# SCH_usb-hub_2024-08-11.net
KiCad netlist of a schematic drawn in EasyEDA
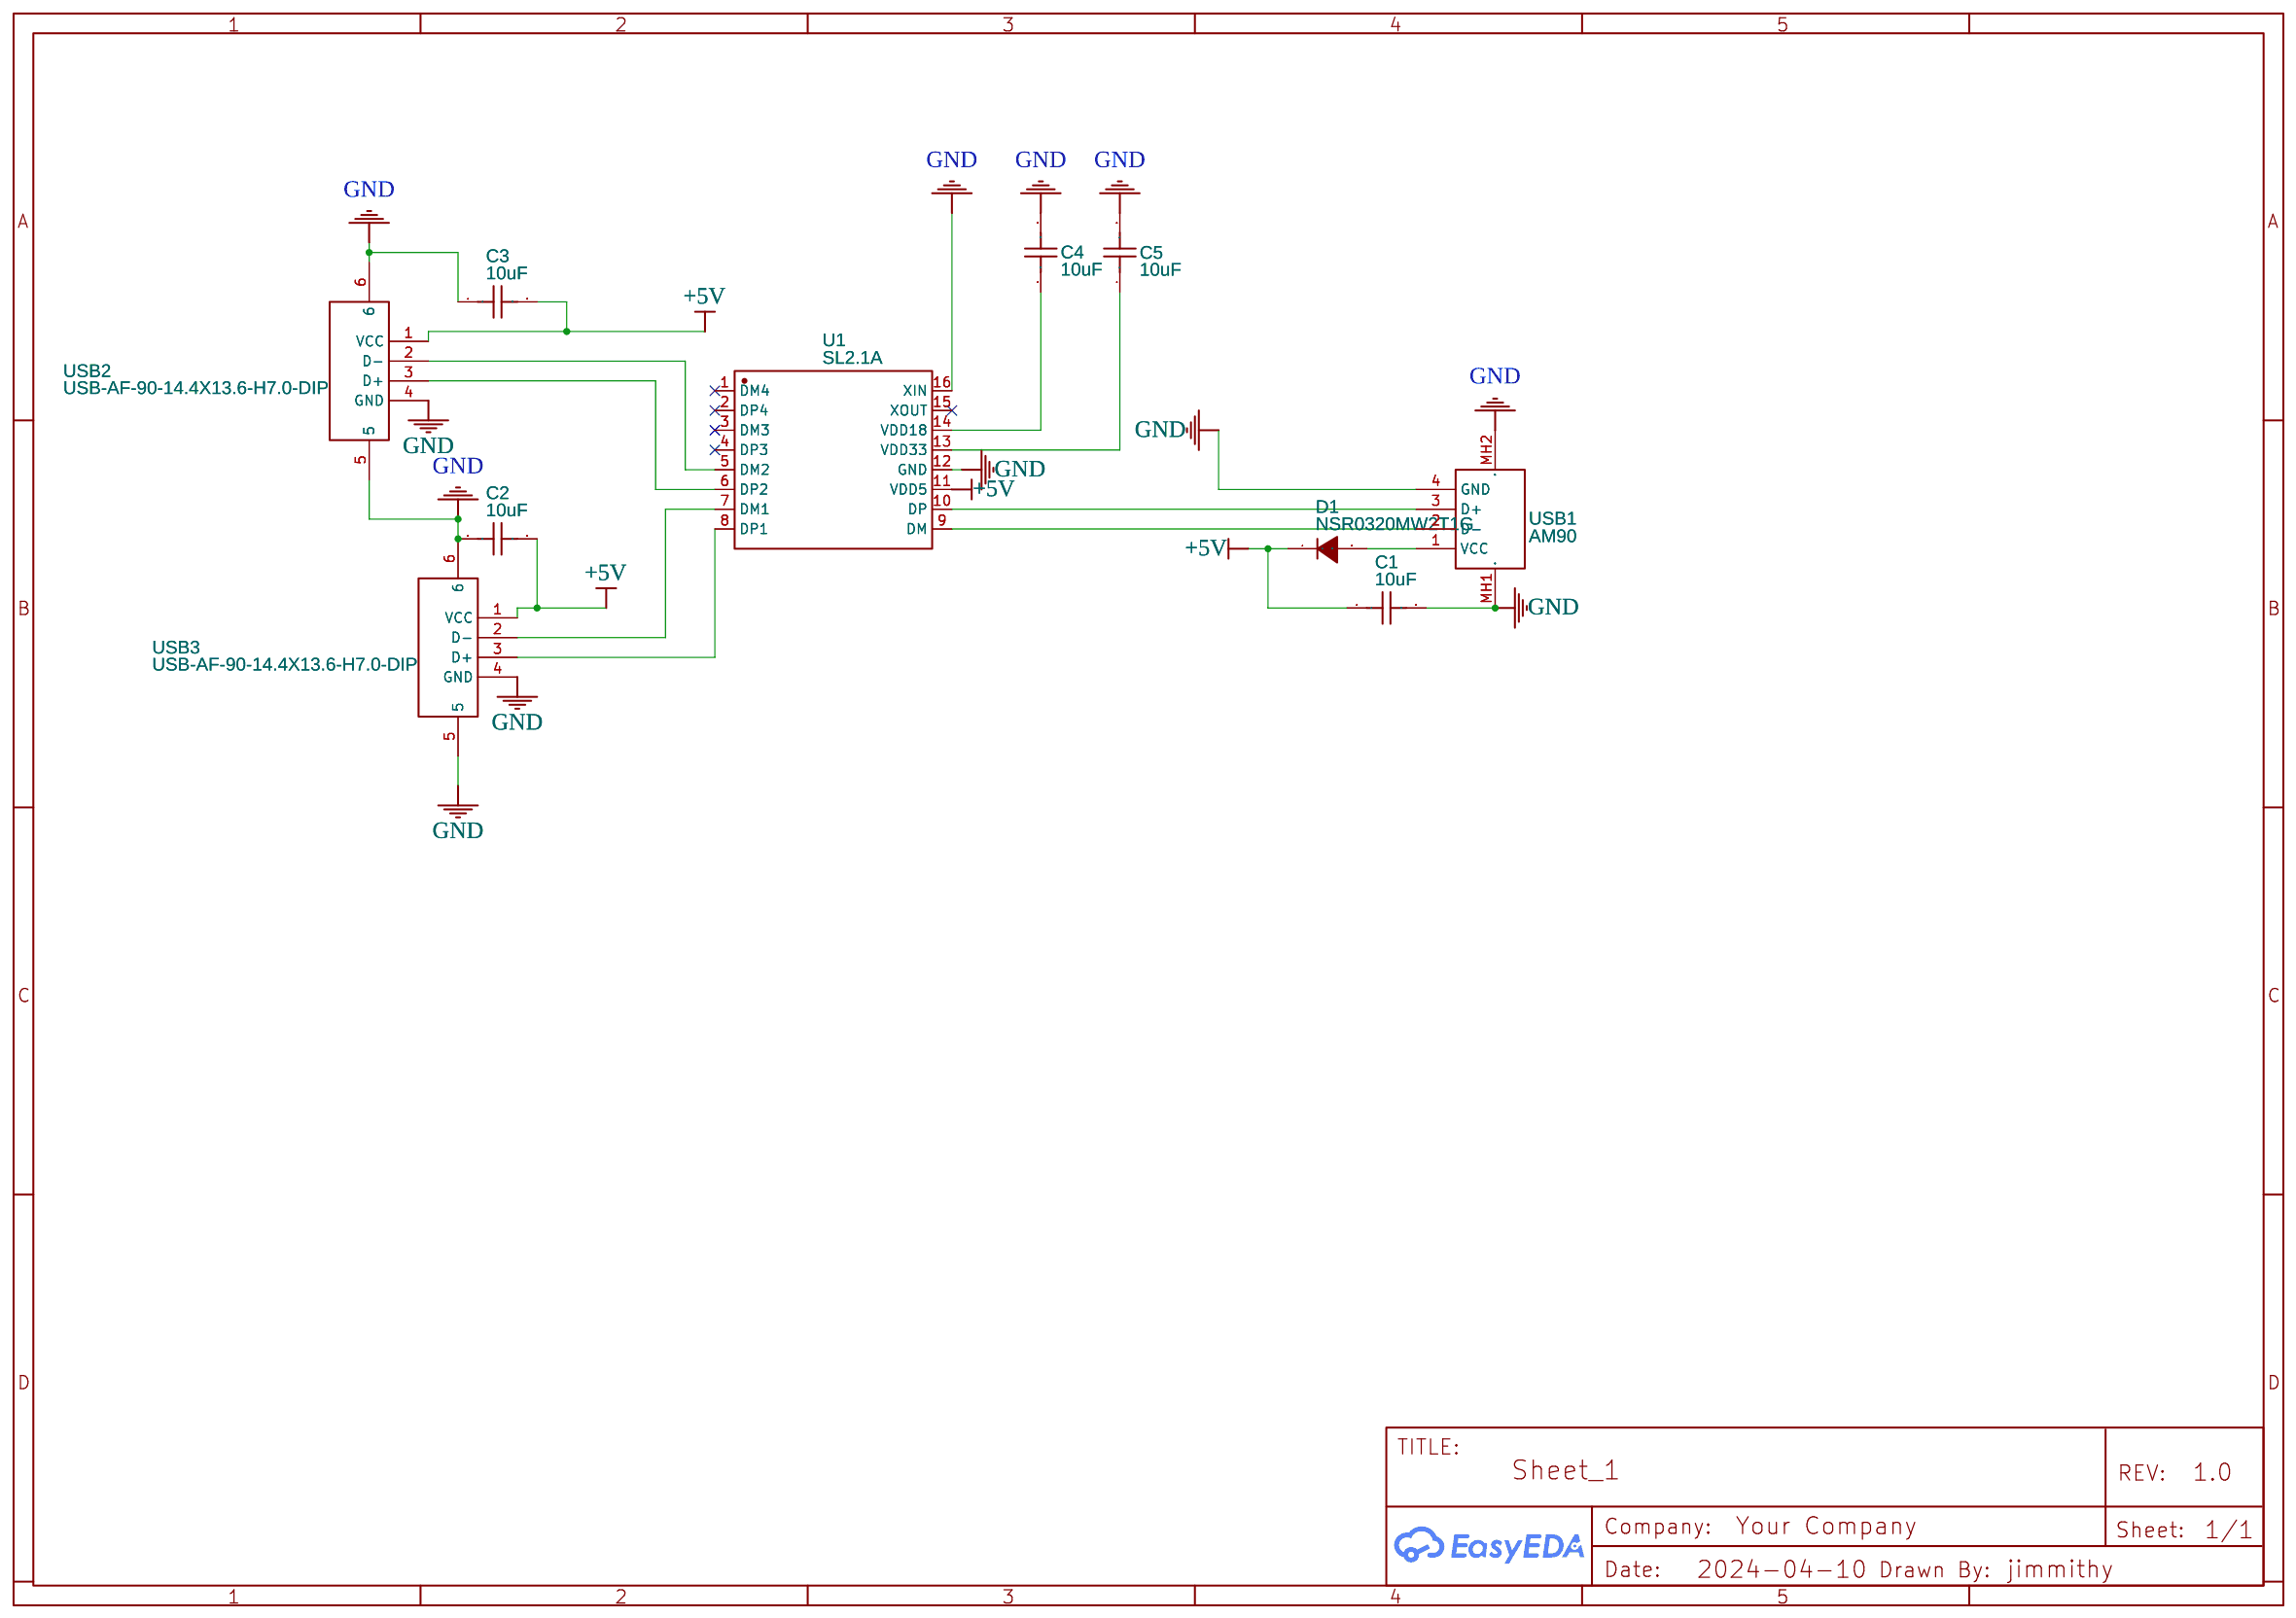
[diagram p0: schematic sheet]

(export (version "E")
  (design (tool "Eeschema 10.0.6"))
  (components
    (comp (ref "C1")
      (value "10uF")
      (fields
        (field (name "Manufacturer Part") "CL10A106KP8NNNC")
        (field (name "Manufacturer") "SAMSUNG(三星)")
      )
      (libsource (lib "") (part "CL10A106KP8NNNC"))
    )
    (comp (ref "C2")
      (value "10uF")
      (fields
        (field (name "Manufacturer Part") "CL10A106KP8NNNC")
        (field (name "Manufacturer") "SAMSUNG(三星)")
      )
      (libsource (lib "") (part "CL10A106KP8NNNC"))
    )
    (comp (ref "C3")
      (value "10uF")
      (fields
        (field (name "Manufacturer Part") "CL10A106KP8NNNC")
        (field (name "Manufacturer") "SAMSUNG(三星)")
      )
      (libsource (lib "") (part "CL10A106KP8NNNC"))
    )
    (comp (ref "C4")
      (value "10uF")
      (fields
        (field (name "Manufacturer Part") "CL10A106KP8NNNC")
        (field (name "Manufacturer") "SAMSUNG(三星)")
      )
      (libsource (lib "") (part "CL10A106KP8NNNC_1"))
    )
    (comp (ref "C5")
      (value "10uF")
      (fields
        (field (name "Manufacturer Part") "CL10A106KP8NNNC")
        (field (name "Manufacturer") "SAMSUNG(三星)")
      )
      (libsource (lib "") (part "CL10A106KP8NNNC_1"))
    )
    (comp (ref "D1")
      (value "NSR0320MW2T1G")
      (fields (field (name "Manufacturer") "onsemi(安森美)"))
      (libsource (lib "") (part "NSR0320MW2T1G"))
    )
    (comp (ref "U1")
      (value "SL2.1A")
      (fields (field (name "Manufacturer") "CoreChips(和芯润德)"))
      (libsource (lib "") (part "SL2.1A"))
    )
    (comp (ref "USB1")
      (value "AM90")
      (fields (field (name "Manufacturer") "SHOU HAN(首韩)"))
      (libsource (lib "") (part "AM90"))
    )
    (comp (ref "USB2")
      (value "USB-AF-90-14.4X13.6-H7.0-DIP")
      (fields (field (name "Manufacturer Part") "903-131A1011D10100") (field (name "Manufacturer") "精拓金"))
      (libsource (lib "") (part "USB-AF-90-14.4X13.6-H7.0-DIP"))
    )
    (comp (ref "USB3")
      (value "USB-AF-90-14.4X13.6-H7.0-DIP")
      (fields (field (name "Manufacturer Part") "903-131A1011D10100") (field (name "Manufacturer") "精拓金"))
      (libsource (lib "") (part "USB-AF-90-14.4X13.6-H7.0-DIP"))
    )
  )
  (nets
    (net (code "1") (name "+5V") (class "Default")
      (node (ref "C1") (pin "1") (pinfunction "1_1") (pintype "unspecified"))
      (node (ref "C2") (pin "2") (pinfunction "2_2") (pintype "unspecified"))
      (node (ref "C3") (pin "2") (pinfunction "2_2") (pintype "unspecified"))
      (node (ref "D1") (pin "1") (pinfunction "C_1") (pintype "unspecified"))
      (node (ref "U1") (pin "11") (pinfunction "VDD5_11") (pintype "unspecified"))
      (node (ref "USB2") (pin "1") (pinfunction "VCC_1") (pintype "unspecified"))
      (node (ref "USB3") (pin "1") (pinfunction "VCC_1") (pintype "unspecified"))
    )
    (net (code "2") (name "GND") (class "Default")
      (node (ref "C1") (pin "2") (pinfunction "2_2") (pintype "unspecified"))
      (node (ref "C2") (pin "1") (pinfunction "1_1") (pintype "unspecified"))
      (node (ref "C3") (pin "1") (pinfunction "1_1") (pintype "unspecified"))
      (node (ref "C4") (pin "2") (pinfunction "2_2") (pintype "unspecified"))
      (node (ref "C5") (pin "2") (pinfunction "2_2") (pintype "unspecified"))
      (node (ref "U1") (pin "12") (pinfunction "GND_12") (pintype "unspecified"))
      (node (ref "U1") (pin "16") (pinfunction "XIN_16") (pintype "unspecified"))
      (node (ref "USB1") (pin "4") (pinfunction "GND_4") (pintype "input"))
      (node (ref "USB1") (pin "MH1") (pinfunction "MH1_MH1") (pintype "unspecified"))
      (node (ref "USB1") (pin "MH2") (pinfunction "MH2_MH2") (pintype "unspecified"))
      (node (ref "USB2") (pin "4") (pinfunction "GND_4") (pintype "unspecified"))
      (node (ref "USB2") (pin "5") (pinfunction "5_5") (pintype "unspecified"))
      (node (ref "USB2") (pin "6") (pinfunction "6_6") (pintype "unspecified"))
      (node (ref "USB3") (pin "4") (pinfunction "GND_4") (pintype "unspecified"))
      (node (ref "USB3") (pin "5") (pinfunction "5_5") (pintype "unspecified"))
      (node (ref "USB3") (pin "6") (pinfunction "6_6") (pintype "unspecified"))
    )
    (net (code "3") (name "Net-(D1-A)") (class "Default")
      (node (ref "D1") (pin "2") (pinfunction "A_2") (pintype "unspecified"))
      (node (ref "USB1") (pin "1") (pinfunction "VCC_1") (pintype "input"))
    )
    (net (code "4") (name "Net-(U1-DM)") (class "Default")
      (node (ref "U1") (pin "9") (pinfunction "DM_9") (pintype "unspecified"))
      (node (ref "USB1") (pin "2") (pinfunction "D-_2") (pintype "input"))
    )
    (net (code "5") (name "Net-(U1-DM1)") (class "Default")
      (node (ref "U1") (pin "7") (pinfunction "DM1_7") (pintype "unspecified"))
      (node (ref "USB3") (pin "2") (pinfunction "D-_2") (pintype "unspecified"))
    )
    (net (code "6") (name "Net-(U1-DM2)") (class "Default")
      (node (ref "U1") (pin "5") (pinfunction "DM2_5") (pintype "unspecified"))
      (node (ref "USB2") (pin "2") (pinfunction "D-_2") (pintype "unspecified"))
    )
    (net (code "7") (name "Net-(U1-DP)") (class "Default")
      (node (ref "U1") (pin "10") (pinfunction "DP_10") (pintype "unspecified"))
      (node (ref "USB1") (pin "3") (pinfunction "D+_3") (pintype "input"))
    )
    (net (code "8") (name "Net-(U1-DP1)") (class "Default")
      (node (ref "U1") (pin "8") (pinfunction "DP1_8") (pintype "unspecified"))
      (node (ref "USB3") (pin "3") (pinfunction "D+_3") (pintype "unspecified"))
    )
    (net (code "9") (name "Net-(U1-DP2)") (class "Default")
      (node (ref "U1") (pin "6") (pinfunction "DP2_6") (pintype "unspecified"))
      (node (ref "USB2") (pin "3") (pinfunction "D+_3") (pintype "unspecified"))
    )
    (net (code "10") (name "Net-(U1-VDD18)") (class "Default")
      (node (ref "C4") (pin "1") (pinfunction "1_1") (pintype "unspecified"))
      (node (ref "U1") (pin "14") (pinfunction "VDD18_14") (pintype "unspecified"))
    )
    (net (code "11") (name "Net-(U1-VDD33)") (class "Default")
      (node (ref "C5") (pin "1") (pinfunction "1_1") (pintype "unspecified"))
      (node (ref "U1") (pin "13") (pinfunction "VDD33_13") (pintype "unspecified"))
    )
    (net (code "12") (name "unconnected-(U1-DM3-Pad3)") (class "Default")
      (node (ref "U1") (pin "3") (pinfunction "DM3_3") (pintype "unspecified+no_connect"))
    )
    (net (code "13") (name "unconnected-(U1-DM4-Pad1)") (class "Default")
      (node (ref "U1") (pin "1") (pinfunction "DM4_1") (pintype "unspecified+no_connect"))
    )
    (net (code "14") (name "unconnected-(U1-DP3-Pad4)") (class "Default")
      (node (ref "U1") (pin "4") (pinfunction "DP3_4") (pintype "unspecified+no_connect"))
    )
    (net (code "15") (name "unconnected-(U1-DP4-Pad2)") (class "Default")
      (node (ref "U1") (pin "2") (pinfunction "DP4_2") (pintype "unspecified+no_connect"))
    )
    (net (code "16") (name "unconnected-(U1-XOUT-Pad15)") (class "Default")
      (node (ref "U1") (pin "15") (pinfunction "XOUT_15") (pintype "unspecified+no_connect"))
    )
  )
)
